# beatbelt.net
KiCad netlist of a schematic drawn in EAGLE
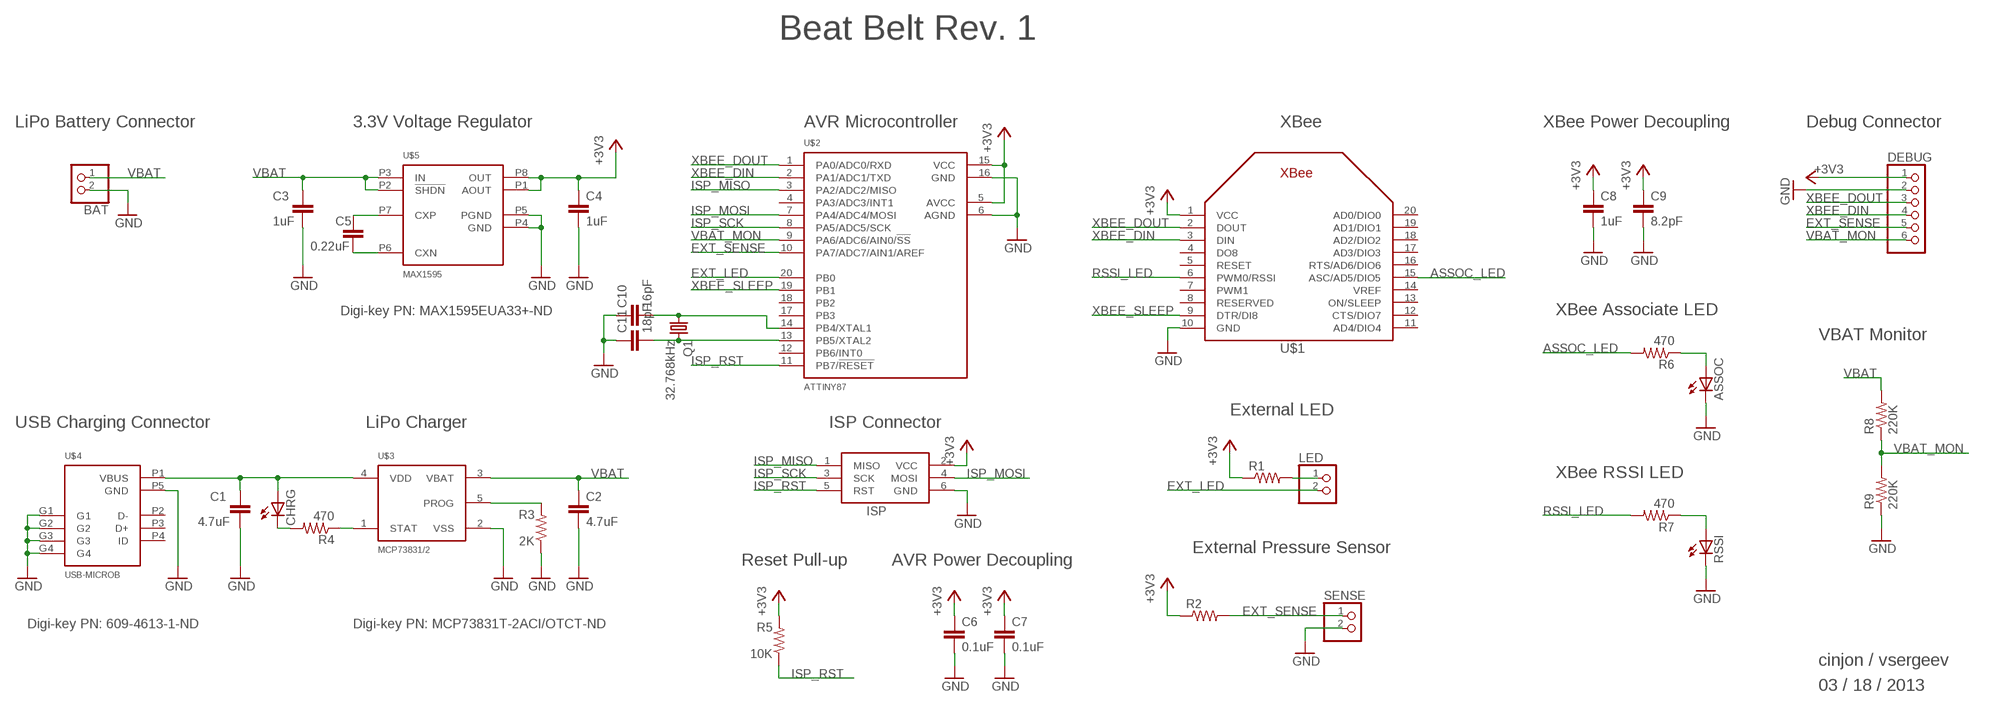
[diagram p0: schematic, sheet 1]

(export (version "E")
  (design (tool "Eeschema 10.0.6"))
  (components
    (comp (ref "ASSOC")
      (value "LEDCHIPLED_0805")
      (footprint "eagle-import:CHIPLED_0805")
      (libsource (lib "eagle-import") (part "LEDCHIPLED_0805"))
    )
    (comp (ref "BAT")
      (value "JST_2PIN-SMT-RA")
      (footprint "eagle-import:JST-PH-2-SMT-RA")
      (libsource (lib "eagle-import") (part "JST_2PIN-SMT-RA"))
    )
    (comp (ref "C1")
      (value "4.7uF")
      (footprint "eagle-import:C0805")
      (libsource (lib "eagle-import") (part "C-EUC0805"))
    )
    (comp (ref "C2")
      (value "4.7uF")
      (footprint "eagle-import:C0805")
      (libsource (lib "eagle-import") (part "C-EUC0805"))
    )
    (comp (ref "C3")
      (value "1uF")
      (footprint "eagle-import:C0805")
      (libsource (lib "eagle-import") (part "C-EUC0805"))
    )
    (comp (ref "C4")
      (value "1uF")
      (footprint "eagle-import:C0805")
      (libsource (lib "eagle-import") (part "C-EUC0805"))
    )
    (comp (ref "C5")
      (value "0.22uF")
      (footprint "eagle-import:C0603")
      (libsource (lib "eagle-import") (part "C-EUC0603"))
    )
    (comp (ref "C6")
      (value "0.1uF")
      (footprint "eagle-import:C0805")
      (libsource (lib "eagle-import") (part "C-EUC0805"))
    )
    (comp (ref "C7")
      (value "0.1uF")
      (footprint "eagle-import:C0805")
      (libsource (lib "eagle-import") (part "C-EUC0805"))
    )
    (comp (ref "C8")
      (value "1uF")
      (footprint "eagle-import:C0805")
      (libsource (lib "eagle-import") (part "C-EUC0805"))
    )
    (comp (ref "C9")
      (value "8.2pF")
      (footprint "eagle-import:C0805")
      (libsource (lib "eagle-import") (part "C-EUC0805"))
    )
    (comp (ref "C10")
      (value "16pF")
      (footprint "eagle-import:C0603")
      (libsource (lib "eagle-import") (part "C-EUC0603"))
    )
    (comp (ref "C11")
      (value "18pF")
      (footprint "eagle-import:C0603")
      (libsource (lib "eagle-import") (part "C-EUC0603"))
    )
    (comp (ref "CHRG")
      (value "LEDCHIPLED_0805")
      (footprint "eagle-import:CHIPLED_0805")
      (libsource (lib "eagle-import") (part "LEDCHIPLED_0805"))
    )
    (comp (ref "DEBUG")
      (value "PINHD-1X6")
      (footprint "eagle-import:1X06")
      (libsource (lib "eagle-import") (part "PINHD-1X6"))
    )
    (comp (ref "ISP")
      (value "AVRISP-6")
      (footprint "eagle-import:AVRISP")
      (libsource (lib "eagle-import") (part "AVRISP-6"))
    )
    (comp (ref "LED")
      (value "PINHD-1X2")
      (footprint "eagle-import:1X02")
      (libsource (lib "eagle-import") (part "PINHD-1X2"))
    )
    (comp (ref "Q1")
      (value "32.768kHz")
      (footprint "eagle-import:TC26V")
      (libsource (lib "eagle-import") (part "CRYSTALTC26V"))
    )
    (comp (ref "R1")
      (value "R-US_R0805")
      (footprint "eagle-import:R0805")
      (libsource (lib "eagle-import") (part "R-US_R0805"))
    )
    (comp (ref "R2")
      (value "R-US_R0805")
      (footprint "eagle-import:R0805")
      (libsource (lib "eagle-import") (part "R-US_R0805"))
    )
    (comp (ref "R3")
      (value "2K")
      (footprint "eagle-import:R0805")
      (libsource (lib "eagle-import") (part "R-US_R0805"))
    )
    (comp (ref "R4")
      (value "470")
      (footprint "eagle-import:R0805")
      (libsource (lib "eagle-import") (part "R-US_R0805"))
    )
    (comp (ref "R5")
      (value "10K")
      (footprint "eagle-import:R0805")
      (libsource (lib "eagle-import") (part "R-US_R0805"))
    )
    (comp (ref "R6")
      (value "470")
      (footprint "eagle-import:R0805")
      (libsource (lib "eagle-import") (part "R-US_R0805"))
    )
    (comp (ref "R7")
      (value "470")
      (footprint "eagle-import:R0805")
      (libsource (lib "eagle-import") (part "R-US_R0805"))
    )
    (comp (ref "R8")
      (value "220K")
      (footprint "eagle-import:R0805")
      (libsource (lib "eagle-import") (part "R-US_R0805"))
    )
    (comp (ref "R9")
      (value "220K")
      (footprint "eagle-import:R0805")
      (libsource (lib "eagle-import") (part "R-US_R0805"))
    )
    (comp (ref "RSSI")
      (value "LEDCHIPLED_0805")
      (footprint "eagle-import:CHIPLED_0805")
      (libsource (lib "eagle-import") (part "LEDCHIPLED_0805"))
    )
    (comp (ref "SENSE")
      (value "PINHD-1X2")
      (footprint "eagle-import:1X02")
      (libsource (lib "eagle-import") (part "PINHD-1X2"))
    )
    (comp (ref "U$1")
      (value "XBEE")
      (footprint "eagle-import:XBEE")
      (libsource (lib "eagle-import") (part "XBEE"))
    )
    (comp (ref "U$2")
      (value "ATTINY87")
      (footprint "eagle-import:SOIC20S")
      (libsource (lib "eagle-import") (part "ATTINY87"))
    )
    (comp (ref "U$3")
      (value "MCP73831/2")
      (footprint "eagle-import:SOT23-5L")
      (libsource (lib "eagle-import") (part "MCP73831/2"))
    )
    (comp (ref "U$4")
      (value "USB-MICROB")
      (footprint "eagle-import:USB-MICROB")
      (libsource (lib "eagle-import") (part "USB-MICROB"))
    )
    (comp (ref "U$5")
      (value "MAX1595")
      (footprint "eagle-import:UMAX8")
      (libsource (lib "eagle-import") (part "MAX1595"))
    )
  )
  (nets
    (net (code "1") (name "+3V3") (class "Default")
      (node (ref "C4") (pin "1") (pinfunction "1_1") (pintype "passive"))
      (node (ref "C6") (pin "1") (pinfunction "1_1") (pintype "passive"))
      (node (ref "C7") (pin "1") (pinfunction "1_1") (pintype "passive"))
      (node (ref "C8") (pin "1") (pinfunction "1_1") (pintype "passive"))
      (node (ref "C9") (pin "1") (pinfunction "1_1") (pintype "passive"))
      (node (ref "DEBUG") (pin "1") (pinfunction "1_1") (pintype "passive"))
      (node (ref "ISP") (pin "2") (pinfunction "VCC_2") (pintype "power_in"))
      (node (ref "R1") (pin "1") (pinfunction "1_1") (pintype "passive"))
      (node (ref "R2") (pin "1") (pinfunction "1_1") (pintype "passive"))
      (node (ref "R5") (pin "2") (pinfunction "2_2") (pintype "passive"))
      (node (ref "U$1") (pin "1") (pinfunction "VCC_1") (pintype "power_in"))
      (node (ref "U$2") (pin "15") (pinfunction "VCC_15") (pintype "bidirectional"))
      (node (ref "U$2") (pin "5") (pinfunction "AVCC_5") (pintype "bidirectional"))
      (node (ref "U$5") (pin "P1") (pinfunction "AOUT_P1") (pintype "bidirectional"))
      (node (ref "U$5") (pin "P8") (pinfunction "OUT_P8") (pintype "bidirectional"))
    )
    (net (code "2") (name "/ASSOC_LED") (class "Default")
      (node (ref "R6") (pin "2") (pinfunction "2_2") (pintype "passive"))
      (node (ref "U$1") (pin "15") (pinfunction "ASC/AD5/DIO5_15") (pintype "bidirectional"))
    )
    (net (code "3") (name "/EXT_LED") (class "Default")
      (node (ref "LED") (pin "2") (pinfunction "2_2") (pintype "passive"))
      (node (ref "U$2") (pin "20") (pinfunction "PB0_20") (pintype "bidirectional"))
    )
    (net (code "4") (name "/EXT_SENSE") (class "Default")
      (node (ref "DEBUG") (pin "5") (pinfunction "5_5") (pintype "passive"))
      (node (ref "R2") (pin "2") (pinfunction "2_2") (pintype "passive"))
      (node (ref "SENSE") (pin "1") (pinfunction "1_1") (pintype "passive"))
      (node (ref "U$2") (pin "10") (pinfunction "PA7/ADC7/AIN1/AREF_10") (pintype "bidirectional"))
    )
    (net (code "5") (name "/ISP_MISO") (class "Default")
      (node (ref "ISP") (pin "1") (pinfunction "MISO_1") (pintype "input"))
      (node (ref "U$2") (pin "3") (pinfunction "PA2/ADC2/MISO_3") (pintype "bidirectional"))
    )
    (net (code "6") (name "/ISP_MOSI") (class "Default")
      (node (ref "ISP") (pin "4") (pinfunction "MOSI_4") (pintype "output"))
      (node (ref "U$2") (pin "7") (pinfunction "PA4/ADC4/MOSI_7") (pintype "bidirectional"))
    )
    (net (code "7") (name "/ISP_RST") (class "Default")
      (node (ref "ISP") (pin "5") (pinfunction "RST_5") (pintype "output"))
      (node (ref "R5") (pin "1") (pinfunction "1_1") (pintype "passive"))
      (node (ref "U$2") (pin "11") (pinfunction "PB7/~{RESET}_11") (pintype "bidirectional"))
    )
    (net (code "8") (name "/ISP_SCK") (class "Default")
      (node (ref "ISP") (pin "3") (pinfunction "SCK_3") (pintype "output"))
      (node (ref "U$2") (pin "8") (pinfunction "PA5/ADC5/SCK_8") (pintype "bidirectional"))
    )
    (net (code "9") (name "/RSSI_LED") (class "Default")
      (node (ref "R7") (pin "2") (pinfunction "2_2") (pintype "passive"))
      (node (ref "U$1") (pin "6") (pinfunction "PWM0/RSSI_6") (pintype "output"))
    )
    (net (code "10") (name "/VBAT") (class "Default")
      (node (ref "BAT") (pin "1") (pinfunction "2_1") (pintype "passive"))
      (node (ref "C2") (pin "1") (pinfunction "1_1") (pintype "passive"))
      (node (ref "C3") (pin "1") (pinfunction "1_1") (pintype "passive"))
      (node (ref "R8") (pin "2") (pinfunction "2_2") (pintype "passive"))
      (node (ref "U$3") (pin "3") (pinfunction "VBAT_3") (pintype "bidirectional"))
      (node (ref "U$5") (pin "P2") (pinfunction "~{SHDN}_P2") (pintype "bidirectional"))
      (node (ref "U$5") (pin "P3") (pinfunction "IN_P3") (pintype "bidirectional"))
    )
    (net (code "11") (name "/VBAT_MON") (class "Default")
      (node (ref "DEBUG") (pin "6") (pinfunction "6_6") (pintype "passive"))
      (node (ref "R8") (pin "1") (pinfunction "1_1") (pintype "passive"))
      (node (ref "R9") (pin "2") (pinfunction "2_2") (pintype "passive"))
      (node (ref "U$2") (pin "9") (pinfunction "PA6/ADC6/AIN0/~{SS}_9") (pintype "bidirectional"))
    )
    (net (code "12") (name "/XBEE_DIN") (class "Default")
      (node (ref "DEBUG") (pin "4") (pinfunction "4_4") (pintype "passive"))
      (node (ref "U$1") (pin "3") (pinfunction "DIN_3") (pintype "input"))
      (node (ref "U$2") (pin "2") (pinfunction "PA1/ADC1/TXD_2") (pintype "bidirectional"))
    )
    (net (code "13") (name "/XBEE_DOUT") (class "Default")
      (node (ref "DEBUG") (pin "3") (pinfunction "3_3") (pintype "passive"))
      (node (ref "U$1") (pin "2") (pinfunction "DOUT_2") (pintype "output"))
      (node (ref "U$2") (pin "1") (pinfunction "PA0/ADC0/RXD_1") (pintype "bidirectional"))
    )
    (net (code "14") (name "/XBEE_SLEEP") (class "Default")
      (node (ref "U$1") (pin "9") (pinfunction "DTR/DI8_9") (pintype "input"))
      (node (ref "U$2") (pin "19") (pinfunction "PB1_19") (pintype "bidirectional"))
    )
    (net (code "15") (name "GND") (class "Default")
      (node (ref "ASSOC") (pin "C") (pinfunction "C_C") (pintype "passive"))
      (node (ref "BAT") (pin "2") (pinfunction "1_2") (pintype "passive"))
      (node (ref "C1") (pin "2") (pinfunction "2_2") (pintype "passive"))
      (node (ref "C10") (pin "1") (pinfunction "1_1") (pintype "passive"))
      (node (ref "C11") (pin "1") (pinfunction "1_1") (pintype "passive"))
      (node (ref "C2") (pin "2") (pinfunction "2_2") (pintype "passive"))
      (node (ref "C3") (pin "2") (pinfunction "2_2") (pintype "passive"))
      (node (ref "C4") (pin "2") (pinfunction "2_2") (pintype "passive"))
      (node (ref "C6") (pin "2") (pinfunction "2_2") (pintype "passive"))
      (node (ref "C7") (pin "2") (pinfunction "2_2") (pintype "passive"))
      (node (ref "C8") (pin "2") (pinfunction "2_2") (pintype "passive"))
      (node (ref "C9") (pin "2") (pinfunction "2_2") (pintype "passive"))
      (node (ref "DEBUG") (pin "2") (pinfunction "2_2") (pintype "passive"))
      (node (ref "ISP") (pin "6") (pinfunction "GND_6") (pintype "power_in"))
      (node (ref "R3") (pin "1") (pinfunction "1_1") (pintype "passive"))
      (node (ref "R9") (pin "1") (pinfunction "1_1") (pintype "passive"))
      (node (ref "RSSI") (pin "C") (pinfunction "C_C") (pintype "passive"))
      (node (ref "SENSE") (pin "2") (pinfunction "2_2") (pintype "passive"))
      (node (ref "U$1") (pin "10") (pinfunction "GND_10") (pintype "power_in"))
      (node (ref "U$2") (pin "16") (pinfunction "GND_16") (pintype "bidirectional"))
      (node (ref "U$2") (pin "6") (pinfunction "AGND_6") (pintype "bidirectional"))
      (node (ref "U$3") (pin "2") (pinfunction "VSS_2") (pintype "bidirectional"))
      (node (ref "U$4") (pin "G1") (pinfunction "G1_G1") (pintype "bidirectional"))
      (node (ref "U$4") (pin "G2") (pinfunction "G2_G2") (pintype "bidirectional"))
      (node (ref "U$4") (pin "G3") (pinfunction "G3_G3") (pintype "bidirectional"))
      (node (ref "U$4") (pin "G4") (pinfunction "G4_G4") (pintype "bidirectional"))
      (node (ref "U$4") (pin "P5") (pinfunction "GND_P5") (pintype "bidirectional"))
      (node (ref "U$5") (pin "P4") (pinfunction "GND_P4") (pintype "bidirectional"))
      (node (ref "U$5") (pin "P5") (pinfunction "PGND_P5") (pintype "bidirectional"))
    )
    (net (code "16") (name "Net-(ASSOC-PadA)") (class "Default")
      (node (ref "ASSOC") (pin "A") (pinfunction "A_A") (pintype "passive"))
      (node (ref "R6") (pin "1") (pinfunction "1_1") (pintype "passive"))
    )
    (net (code "17") (name "Net-(CHRG-PadC)") (class "Default")
      (node (ref "CHRG") (pin "C") (pinfunction "C_C") (pintype "passive"))
      (node (ref "R4") (pin "2") (pinfunction "2_2") (pintype "passive"))
    )
    (net (code "18") (name "Net-(LED-Pad1)") (class "Default")
      (node (ref "LED") (pin "1") (pinfunction "1_1") (pintype "passive"))
      (node (ref "R1") (pin "2") (pinfunction "2_2") (pintype "passive"))
    )
    (net (code "19") (name "Net-(R7-Pad1)") (class "Default")
      (node (ref "R7") (pin "1") (pinfunction "1_1") (pintype "passive"))
      (node (ref "RSSI") (pin "A") (pinfunction "A_A") (pintype "passive"))
    )
    (net (code "20") (name "Net-(U$2-PB4{slash}XTAL1)") (class "Default")
      (node (ref "C10") (pin "2") (pinfunction "2_2") (pintype "passive"))
      (node (ref "Q1") (pin "1") (pinfunction "1_1") (pintype "passive"))
      (node (ref "U$2") (pin "14") (pinfunction "PB4/XTAL1_14") (pintype "bidirectional"))
    )
    (net (code "21") (name "Net-(U$2-PB5{slash}XTAL2)") (class "Default")
      (node (ref "C11") (pin "2") (pinfunction "2_2") (pintype "passive"))
      (node (ref "Q1") (pin "2") (pinfunction "2_2") (pintype "passive"))
      (node (ref "U$2") (pin "13") (pinfunction "PB5/XTAL2_13") (pintype "bidirectional"))
    )
    (net (code "22") (name "Net-(U$3-PROG)") (class "Default")
      (node (ref "R3") (pin "2") (pinfunction "2_2") (pintype "passive"))
      (node (ref "U$3") (pin "5") (pinfunction "PROG_5") (pintype "bidirectional"))
    )
    (net (code "23") (name "Net-(U$3-STAT)") (class "Default")
      (node (ref "R4") (pin "1") (pinfunction "1_1") (pintype "passive"))
      (node (ref "U$3") (pin "1") (pinfunction "STAT_1") (pintype "bidirectional"))
    )
    (net (code "24") (name "Net-(U$3-VDD)") (class "Default")
      (node (ref "C1") (pin "1") (pinfunction "1_1") (pintype "passive"))
      (node (ref "CHRG") (pin "A") (pinfunction "A_A") (pintype "passive"))
      (node (ref "U$3") (pin "4") (pinfunction "VDD_4") (pintype "bidirectional"))
      (node (ref "U$4") (pin "P1") (pinfunction "VBUS_P1") (pintype "bidirectional"))
    )
    (net (code "25") (name "Net-(U$5-CXN)") (class "Default")
      (node (ref "C5") (pin "2") (pinfunction "2_2") (pintype "passive"))
      (node (ref "U$5") (pin "P6") (pinfunction "CXN_P6") (pintype "bidirectional"))
    )
    (net (code "26") (name "Net-(U$5-CXP)") (class "Default")
      (node (ref "C5") (pin "1") (pinfunction "1_1") (pintype "passive"))
      (node (ref "U$5") (pin "P7") (pinfunction "CXP_P7") (pintype "bidirectional"))
    )
    (net (code "27") (name "unconnected-(U$1-AD0{slash}DIO0-Pad20)") (class "Default")
      (node (ref "U$1") (pin "20") (pinfunction "AD0/DIO0_20") (pintype "bidirectional"))
    )
    (net (code "28") (name "unconnected-(U$1-AD1{slash}DIO1-Pad19)") (class "Default")
      (node (ref "U$1") (pin "19") (pinfunction "AD1/DIO1_19") (pintype "bidirectional"))
    )
    (net (code "29") (name "unconnected-(U$1-AD2{slash}DIO2-Pad18)") (class "Default")
      (node (ref "U$1") (pin "18") (pinfunction "AD2/DIO2_18") (pintype "bidirectional"))
    )
    (net (code "30") (name "unconnected-(U$1-AD3{slash}DIO3-Pad17)") (class "Default")
      (node (ref "U$1") (pin "17") (pinfunction "AD3/DIO3_17") (pintype "bidirectional"))
    )
    (net (code "31") (name "unconnected-(U$1-AD4{slash}DIO4-Pad11)") (class "Default")
      (node (ref "U$1") (pin "11") (pinfunction "AD4/DIO4_11") (pintype "bidirectional"))
    )
    (net (code "32") (name "unconnected-(U$1-CTS{slash}DIO7-Pad12)") (class "Default")
      (node (ref "U$1") (pin "12") (pinfunction "CTS/DIO7_12") (pintype "bidirectional"))
    )
    (net (code "33") (name "unconnected-(U$1-DO8-Pad4)") (class "Default")
      (node (ref "U$1") (pin "4") (pinfunction "DO8_4") (pintype "output"))
    )
    (net (code "34") (name "unconnected-(U$1-ON{slash}SLEEP-Pad13)") (class "Default")
      (node (ref "U$1") (pin "13") (pinfunction "ON/SLEEP_13") (pintype "output"))
    )
    (net (code "35") (name "unconnected-(U$1-PWM1-Pad7)") (class "Default")
      (node (ref "U$1") (pin "7") (pinfunction "PWM1_7") (pintype "output"))
    )
    (net (code "36") (name "unconnected-(U$1-RESERVED-Pad8)") (class "Default")
      (node (ref "U$1") (pin "8") (pinfunction "RESERVED_8") (pintype "no_connect"))
    )
    (net (code "37") (name "unconnected-(U$1-RESET-Pad5)") (class "Default")
      (node (ref "U$1") (pin "5") (pinfunction "RESET_5") (pintype "input"))
    )
    (net (code "38") (name "unconnected-(U$1-RTS{slash}AD6{slash}DIO6-Pad16)") (class "Default")
      (node (ref "U$1") (pin "16") (pinfunction "RTS/AD6/DIO6_16") (pintype "bidirectional"))
    )
    (net (code "39") (name "unconnected-(U$1-VREF-Pad14)") (class "Default")
      (node (ref "U$1") (pin "14") (pinfunction "VREF_14") (pintype "input"))
    )
    (net (code "40") (name "unconnected-(U$2-PA3{slash}ADC3{slash}INT1-Pad4)") (class "Default")
      (node (ref "U$2") (pin "4") (pinfunction "PA3/ADC3/INT1_4") (pintype "bidirectional"))
    )
    (net (code "41") (name "unconnected-(U$2-PB2-Pad18)") (class "Default")
      (node (ref "U$2") (pin "18") (pinfunction "PB2_18") (pintype "bidirectional"))
    )
    (net (code "42") (name "unconnected-(U$2-PB3-Pad17)") (class "Default")
      (node (ref "U$2") (pin "17") (pinfunction "PB3_17") (pintype "bidirectional"))
    )
    (net (code "43") (name "unconnected-(U$2-PB6{slash}INT0-Pad12)") (class "Default")
      (node (ref "U$2") (pin "12") (pinfunction "PB6/INT0_12") (pintype "bidirectional"))
    )
    (net (code "44") (name "unconnected-(U$4-D+-PadP3)") (class "Default")
      (node (ref "U$4") (pin "P3") (pinfunction "D+_P3") (pintype "bidirectional"))
    )
    (net (code "45") (name "unconnected-(U$4-D--PadP2)") (class "Default")
      (node (ref "U$4") (pin "P2") (pinfunction "D-_P2") (pintype "bidirectional"))
    )
    (net (code "46") (name "unconnected-(U$4-ID-PadP4)") (class "Default")
      (node (ref "U$4") (pin "P4") (pinfunction "ID_P4") (pintype "bidirectional"))
    )
  )
)
